# Display.net
KiCad netlist of a schematic drawn in Altium Designer
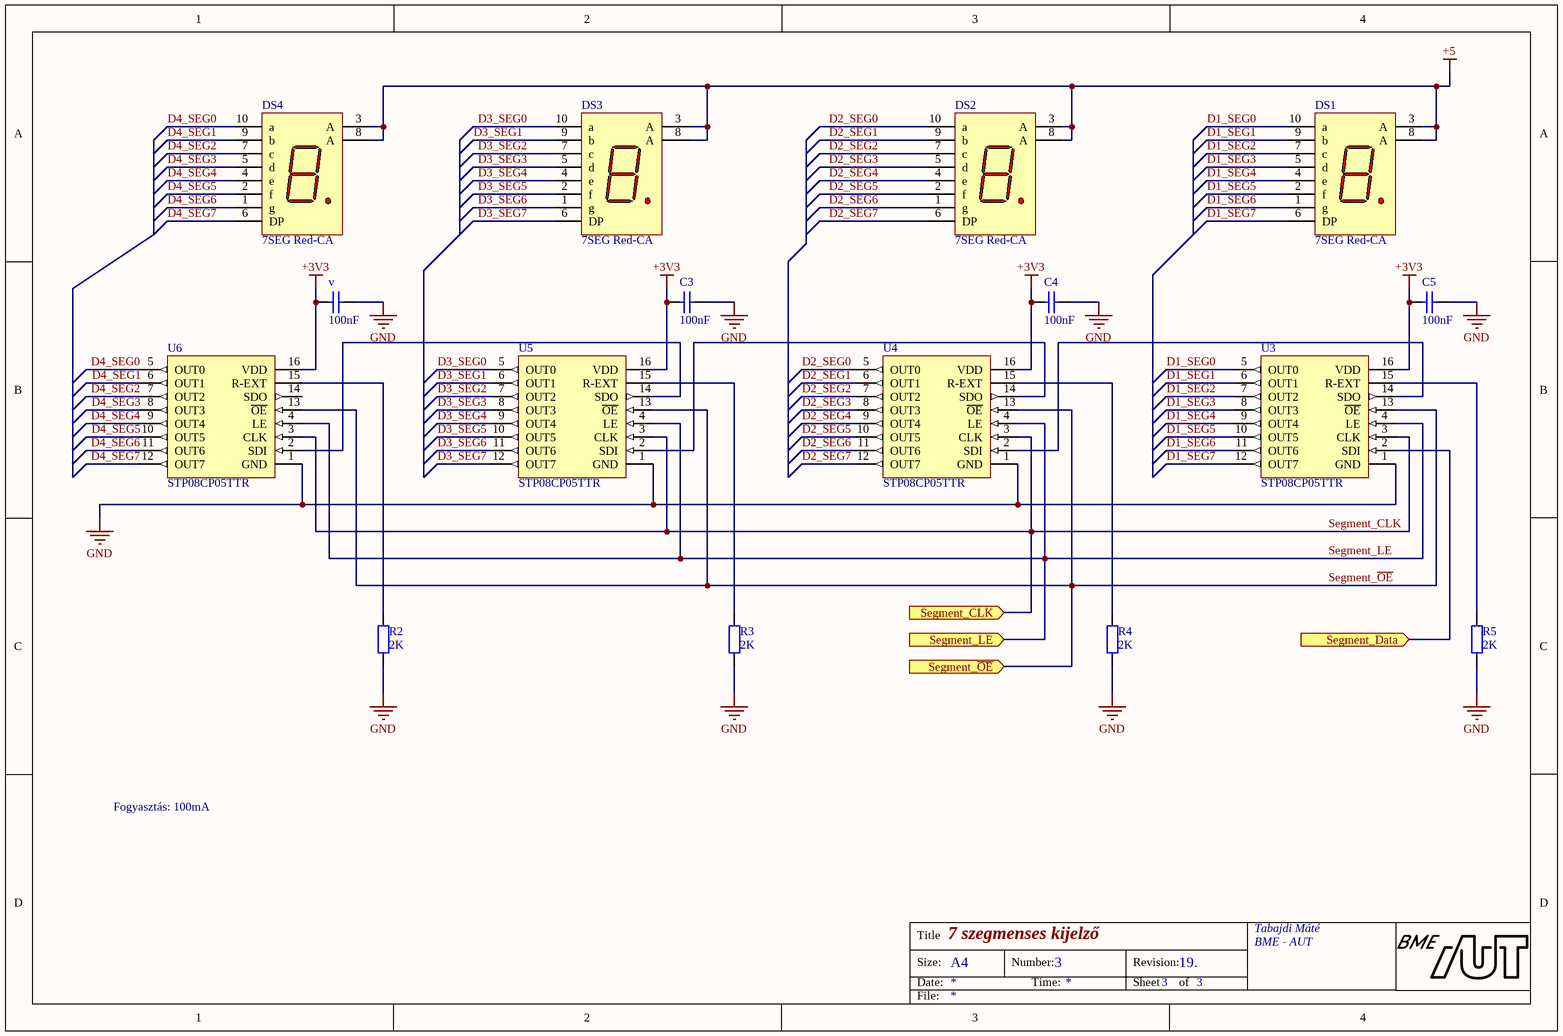
[diagram p0: Display.SchDoc]

(export (version "E")
  (design (tool "Eeschema 10.0.6"))
  (components
    (comp (ref "C3")
      (value "100nF")
      (footprint "FP_0805_CAP_085")
      (description "Capacitor")
      (fields (field (name "TOLERANCE") "10%") (field (name "VOLTAGE") "50V"))
      (libsource (lib "hallglib") (part "CAP"))
    )
    (comp (ref "C4")
      (value "100nF")
      (footprint "FP_0805_CAP_085")
      (description "Capacitor")
      (fields (field (name "TOLERANCE") "10%") (field (name "VOLTAGE") "50V"))
      (libsource (lib "hallglib") (part "CAP"))
    )
    (comp (ref "C5")
      (value "100nF")
      (footprint "FP_0805_CAP_085")
      (description "Capacitor")
      (fields (field (name "TOLERANCE") "10%") (field (name "VOLTAGE") "50V"))
      (libsource (lib "hallglib") (part "CAP"))
    )
    (comp (ref "DS1")
      (value "7SEG Red-CA")
      (footprint "FP_7SEG")
      (description "7-Segment Display: CA, RH DP")
      (fields (field (name "PUBLISHER") "Altium Limited"))
      (libsource (lib "hallglib") (part "7SEG Red-CA"))
    )
    (comp (ref "DS2")
      (value "7SEG Red-CA")
      (footprint "FP_7SEG")
      (description "7-Segment Display: CA, RH DP")
      (fields (field (name "PUBLISHER") "Altium Limited"))
      (libsource (lib "hallglib") (part "7SEG Red-CA"))
    )
    (comp (ref "DS3")
      (value "7SEG Red-CA")
      (footprint "FP_7SEG")
      (description "7-Segment Display: CA, RH DP")
      (fields (field (name "PUBLISHER") "Altium Limited"))
      (libsource (lib "hallglib") (part "7SEG Red-CA"))
    )
    (comp (ref "DS4")
      (value "7SEG Red-CA")
      (footprint "FP_7SEG")
      (description "7-Segment Display: CA, RH DP")
      (fields (field (name "PUBLISHER") "Altium Limited"))
      (libsource (lib "hallglib") (part "7SEG Red-CA"))
    )
    (comp (ref "R2")
      (value "2K")
      (footprint "FP_0805_RES")
      (description "Resistor")
      (fields (field (name "TOLERANCE") "5%") (field (name "POWER") "0.125W"))
      (libsource (lib "hallglib") (part "RES"))
    )
    (comp (ref "R3")
      (value "2K")
      (footprint "FP_0805_RES")
      (description "Resistor")
      (fields (field (name "TOLERANCE") "5%") (field (name "POWER") "0.125W"))
      (libsource (lib "hallglib") (part "RES"))
    )
    (comp (ref "R4")
      (value "2K")
      (footprint "FP_0805_RES")
      (description "Resistor")
      (fields (field (name "TOLERANCE") "5%") (field (name "POWER") "0.125W"))
      (libsource (lib "hallglib") (part "RES"))
    )
    (comp (ref "R5")
      (value "2K")
      (footprint "FP_0805_RES")
      (description "Resistor")
      (fields (field (name "TOLERANCE") "5%") (field (name "POWER") "0.125W"))
      (libsource (lib "hallglib") (part "RES"))
    )
    (comp (ref "U3")
      (value "STP08CP05TTR")
      (footprint "TSOP65P640X120-16M")
      (description "Low voltage, low current power 8-bit shift register")
      (libsource (lib "hallglib") (part "STP08CP05TTR"))
    )
    (comp (ref "U4")
      (value "STP08CP05TTR")
      (footprint "TSOP65P640X120-16M")
      (description "Low voltage, low current power 8-bit shift register")
      (libsource (lib "hallglib") (part "STP08CP05TTR"))
    )
    (comp (ref "U5")
      (value "STP08CP05TTR")
      (footprint "TSOP65P640X120-16M")
      (description "Low voltage, low current power 8-bit shift register")
      (libsource (lib "hallglib") (part "STP08CP05TTR"))
    )
    (comp (ref "U6")
      (value "STP08CP05TTR")
      (footprint "TSOP65P640X120-16M")
      (description "Low voltage, low current power 8-bit shift register")
      (libsource (lib "hallglib") (part "STP08CP05TTR"))
    )
    (comp (ref "v")
      (value "100nF")
      (footprint "FP_0805_CAP_085")
      (description "Capacitor")
      (fields (field (name "TOLERANCE") "10%") (field (name "VOLTAGE") "50V"))
      (libsource (lib "hallglib") (part "CAP"))
    )
  )
  (nets
    (net (code "1") (name "+3V3") (class "Default")
      (node (ref "C3") (pin "2") (pinfunction "2_2") (pintype "passive"))
      (node (ref "C4") (pin "2") (pinfunction "2_2") (pintype "passive"))
      (node (ref "C5") (pin "2") (pinfunction "2_2") (pintype "passive"))
      (node (ref "U3") (pin "16") (pinfunction "VDD_16") (pintype "power_in"))
      (node (ref "U4") (pin "16") (pinfunction "VDD_16") (pintype "power_in"))
      (node (ref "U5") (pin "16") (pinfunction "VDD_16") (pintype "power_in"))
      (node (ref "U6") (pin "16") (pinfunction "VDD_16") (pintype "power_in"))
      (node (ref "v") (pin "2") (pinfunction "2_2") (pintype "passive"))
    )
    (net (code "2") (name "+5") (class "Default")
      (node (ref "DS1") (pin "3") (pinfunction "A_3") (pintype "passive"))
      (node (ref "DS1") (pin "8") (pinfunction "A_8") (pintype "passive"))
      (node (ref "DS2") (pin "3") (pinfunction "A_3") (pintype "passive"))
      (node (ref "DS2") (pin "8") (pinfunction "A_8") (pintype "passive"))
      (node (ref "DS3") (pin "3") (pinfunction "A_3") (pintype "passive"))
      (node (ref "DS3") (pin "8") (pinfunction "A_8") (pintype "passive"))
      (node (ref "DS4") (pin "3") (pinfunction "A_3") (pintype "passive"))
      (node (ref "DS4") (pin "8") (pinfunction "A_8") (pintype "passive"))
    )
    (net (code "3") (name "/D1_SEG0") (class "Default")
      (node (ref "DS1") (pin "10") (pinfunction "a_10") (pintype "passive"))
      (node (ref "U3") (pin "5") (pinfunction "OUT0_5") (pintype "output"))
    )
    (net (code "4") (name "/D1_SEG1") (class "Default")
      (node (ref "DS1") (pin "9") (pinfunction "b_9") (pintype "passive"))
      (node (ref "U3") (pin "6") (pinfunction "OUT1_6") (pintype "output"))
    )
    (net (code "5") (name "/D1_SEG2") (class "Default")
      (node (ref "DS1") (pin "7") (pinfunction "c_7") (pintype "passive"))
      (node (ref "U3") (pin "7") (pinfunction "OUT2_7") (pintype "output"))
    )
    (net (code "6") (name "/D1_SEG3") (class "Default")
      (node (ref "DS1") (pin "5") (pinfunction "d_5") (pintype "passive"))
      (node (ref "U3") (pin "8") (pinfunction "OUT3_8") (pintype "output"))
    )
    (net (code "7") (name "/D1_SEG4") (class "Default")
      (node (ref "DS1") (pin "4") (pinfunction "e_4") (pintype "passive"))
      (node (ref "U3") (pin "9") (pinfunction "OUT4_9") (pintype "output"))
    )
    (net (code "8") (name "/D1_SEG5") (class "Default")
      (node (ref "DS1") (pin "2") (pinfunction "f_2") (pintype "passive"))
      (node (ref "U3") (pin "10") (pinfunction "OUT5_10") (pintype "output"))
    )
    (net (code "9") (name "/D1_SEG6") (class "Default")
      (node (ref "DS1") (pin "1") (pinfunction "g_1") (pintype "passive"))
      (node (ref "U3") (pin "11") (pinfunction "OUT6_11") (pintype "output"))
    )
    (net (code "10") (name "/D1_SEG7") (class "Default")
      (node (ref "DS1") (pin "6") (pinfunction "DP_6") (pintype "passive"))
      (node (ref "U3") (pin "12") (pinfunction "OUT7_12") (pintype "output"))
    )
    (net (code "11") (name "/D2_SEG0") (class "Default")
      (node (ref "DS2") (pin "10") (pinfunction "a_10") (pintype "passive"))
      (node (ref "U4") (pin "5") (pinfunction "OUT0_5") (pintype "output"))
    )
    (net (code "12") (name "/D2_SEG1") (class "Default")
      (node (ref "DS2") (pin "9") (pinfunction "b_9") (pintype "passive"))
      (node (ref "U4") (pin "6") (pinfunction "OUT1_6") (pintype "output"))
    )
    (net (code "13") (name "/D2_SEG2") (class "Default")
      (node (ref "DS2") (pin "7") (pinfunction "c_7") (pintype "passive"))
      (node (ref "U4") (pin "7") (pinfunction "OUT2_7") (pintype "output"))
    )
    (net (code "14") (name "/D2_SEG3") (class "Default")
      (node (ref "DS2") (pin "5") (pinfunction "d_5") (pintype "passive"))
      (node (ref "U4") (pin "8") (pinfunction "OUT3_8") (pintype "output"))
    )
    (net (code "15") (name "/D2_SEG4") (class "Default")
      (node (ref "DS2") (pin "4") (pinfunction "e_4") (pintype "passive"))
      (node (ref "U4") (pin "9") (pinfunction "OUT4_9") (pintype "output"))
    )
    (net (code "16") (name "/D2_SEG5") (class "Default")
      (node (ref "DS2") (pin "2") (pinfunction "f_2") (pintype "passive"))
      (node (ref "U4") (pin "10") (pinfunction "OUT5_10") (pintype "output"))
    )
    (net (code "17") (name "/D2_SEG6") (class "Default")
      (node (ref "DS2") (pin "1") (pinfunction "g_1") (pintype "passive"))
      (node (ref "U4") (pin "11") (pinfunction "OUT6_11") (pintype "output"))
    )
    (net (code "18") (name "/D2_SEG7") (class "Default")
      (node (ref "DS2") (pin "6") (pinfunction "DP_6") (pintype "passive"))
      (node (ref "U4") (pin "12") (pinfunction "OUT7_12") (pintype "output"))
    )
    (net (code "19") (name "/D3_SEG0") (class "Default")
      (node (ref "DS3") (pin "10") (pinfunction "a_10") (pintype "passive"))
      (node (ref "U5") (pin "5") (pinfunction "OUT0_5") (pintype "output"))
    )
    (net (code "20") (name "/D3_SEG1") (class "Default")
      (node (ref "DS3") (pin "9") (pinfunction "b_9") (pintype "passive"))
      (node (ref "U5") (pin "6") (pinfunction "OUT1_6") (pintype "output"))
    )
    (net (code "21") (name "/D3_SEG2") (class "Default")
      (node (ref "DS3") (pin "7") (pinfunction "c_7") (pintype "passive"))
      (node (ref "U5") (pin "7") (pinfunction "OUT2_7") (pintype "output"))
    )
    (net (code "22") (name "/D3_SEG3") (class "Default")
      (node (ref "DS3") (pin "5") (pinfunction "d_5") (pintype "passive"))
      (node (ref "U5") (pin "8") (pinfunction "OUT3_8") (pintype "output"))
    )
    (net (code "23") (name "/D3_SEG4") (class "Default")
      (node (ref "DS3") (pin "4") (pinfunction "e_4") (pintype "passive"))
      (node (ref "U5") (pin "9") (pinfunction "OUT4_9") (pintype "output"))
    )
    (net (code "24") (name "/D3_SEG5") (class "Default")
      (node (ref "DS3") (pin "2") (pinfunction "f_2") (pintype "passive"))
      (node (ref "U5") (pin "10") (pinfunction "OUT5_10") (pintype "output"))
    )
    (net (code "25") (name "/D3_SEG6") (class "Default")
      (node (ref "DS3") (pin "1") (pinfunction "g_1") (pintype "passive"))
      (node (ref "U5") (pin "11") (pinfunction "OUT6_11") (pintype "output"))
    )
    (net (code "26") (name "/D3_SEG7") (class "Default")
      (node (ref "DS3") (pin "6") (pinfunction "DP_6") (pintype "passive"))
      (node (ref "U5") (pin "12") (pinfunction "OUT7_12") (pintype "output"))
    )
    (net (code "27") (name "/D4_SEG0") (class "Default")
      (node (ref "DS4") (pin "10") (pinfunction "a_10") (pintype "passive"))
      (node (ref "U6") (pin "5") (pinfunction "OUT0_5") (pintype "output"))
    )
    (net (code "28") (name "/D4_SEG1") (class "Default")
      (node (ref "DS4") (pin "9") (pinfunction "b_9") (pintype "passive"))
      (node (ref "U6") (pin "6") (pinfunction "OUT1_6") (pintype "output"))
    )
    (net (code "29") (name "/D4_SEG2") (class "Default")
      (node (ref "DS4") (pin "7") (pinfunction "c_7") (pintype "passive"))
      (node (ref "U6") (pin "7") (pinfunction "OUT2_7") (pintype "output"))
    )
    (net (code "30") (name "/D4_SEG3") (class "Default")
      (node (ref "DS4") (pin "5") (pinfunction "d_5") (pintype "passive"))
      (node (ref "U6") (pin "8") (pinfunction "OUT3_8") (pintype "output"))
    )
    (net (code "31") (name "/D4_SEG4") (class "Default")
      (node (ref "DS4") (pin "4") (pinfunction "e_4") (pintype "passive"))
      (node (ref "U6") (pin "9") (pinfunction "OUT4_9") (pintype "output"))
    )
    (net (code "32") (name "/D4_SEG5") (class "Default")
      (node (ref "DS4") (pin "2") (pinfunction "f_2") (pintype "passive"))
      (node (ref "U6") (pin "10") (pinfunction "OUT5_10") (pintype "output"))
    )
    (net (code "33") (name "/D4_SEG6") (class "Default")
      (node (ref "DS4") (pin "1") (pinfunction "g_1") (pintype "passive"))
      (node (ref "U6") (pin "11") (pinfunction "OUT6_11") (pintype "output"))
    )
    (net (code "34") (name "/D4_SEG7") (class "Default")
      (node (ref "DS4") (pin "6") (pinfunction "DP_6") (pintype "passive"))
      (node (ref "U6") (pin "12") (pinfunction "OUT7_12") (pintype "output"))
    )
    (net (code "35") (name "/Segment_CLK") (class "Default")
      (node (ref "U3") (pin "3") (pinfunction "CLK_3") (pintype "input"))
      (node (ref "U4") (pin "3") (pinfunction "CLK_3") (pintype "input"))
      (node (ref "U5") (pin "3") (pinfunction "CLK_3") (pintype "input"))
      (node (ref "U6") (pin "3") (pinfunction "CLK_3") (pintype "input"))
    )
    (net (code "36") (name "/Segment_Data") (class "Default")
      (node (ref "U3") (pin "2") (pinfunction "SDI_2") (pintype "input"))
    )
    (net (code "37") (name "/Segment_LE") (class "Default")
      (node (ref "U3") (pin "4") (pinfunction "LE_4") (pintype "input"))
      (node (ref "U4") (pin "4") (pinfunction "LE_4") (pintype "input"))
      (node (ref "U5") (pin "4") (pinfunction "LE_4") (pintype "input"))
      (node (ref "U6") (pin "4") (pinfunction "LE_4") (pintype "input"))
    )
    (net (code "38") (name "/Segment_~{OE}") (class "Default")
      (node (ref "U3") (pin "13") (pinfunction "~{OE}_13") (pintype "input"))
      (node (ref "U4") (pin "13") (pinfunction "~{OE}_13") (pintype "input"))
      (node (ref "U5") (pin "13") (pinfunction "~{OE}_13") (pintype "input"))
      (node (ref "U6") (pin "13") (pinfunction "~{OE}_13") (pintype "input"))
    )
    (net (code "39") (name "GND") (class "Default")
      (node (ref "C3") (pin "1") (pinfunction "1_1") (pintype "passive"))
      (node (ref "C4") (pin "1") (pinfunction "1_1") (pintype "passive"))
      (node (ref "C5") (pin "1") (pinfunction "1_1") (pintype "passive"))
      (node (ref "R2") (pin "1") (pinfunction "1_1") (pintype "passive"))
      (node (ref "R3") (pin "1") (pinfunction "1_1") (pintype "passive"))
      (node (ref "R4") (pin "1") (pinfunction "1_1") (pintype "passive"))
      (node (ref "R5") (pin "1") (pinfunction "1_1") (pintype "passive"))
      (node (ref "U3") (pin "1") (pinfunction "GND_1") (pintype "passive"))
      (node (ref "U4") (pin "1") (pinfunction "GND_1") (pintype "passive"))
      (node (ref "U5") (pin "1") (pinfunction "GND_1") (pintype "passive"))
      (node (ref "U6") (pin "1") (pinfunction "GND_1") (pintype "passive"))
      (node (ref "v") (pin "1") (pinfunction "1_1") (pintype "passive"))
    )
    (net (code "40") (name "Net-(U3-R-EXT)") (class "Default")
      (node (ref "R5") (pin "2") (pinfunction "2_2") (pintype "passive"))
      (node (ref "U3") (pin "15") (pinfunction "R-EXT_15") (pintype "passive"))
    )
    (net (code "41") (name "Net-(U3-SDO)") (class "Default")
      (node (ref "U3") (pin "14") (pinfunction "SDO_14") (pintype "output"))
      (node (ref "U4") (pin "2") (pinfunction "SDI_2") (pintype "input"))
    )
    (net (code "42") (name "Net-(U4-R-EXT)") (class "Default")
      (node (ref "R4") (pin "2") (pinfunction "2_2") (pintype "passive"))
      (node (ref "U4") (pin "15") (pinfunction "R-EXT_15") (pintype "passive"))
    )
    (net (code "43") (name "Net-(U4-SDO)") (class "Default")
      (node (ref "U4") (pin "14") (pinfunction "SDO_14") (pintype "output"))
      (node (ref "U5") (pin "2") (pinfunction "SDI_2") (pintype "input"))
    )
    (net (code "44") (name "Net-(U5-R-EXT)") (class "Default")
      (node (ref "R3") (pin "2") (pinfunction "2_2") (pintype "passive"))
      (node (ref "U5") (pin "15") (pinfunction "R-EXT_15") (pintype "passive"))
    )
    (net (code "45") (name "Net-(U5-SDO)") (class "Default")
      (node (ref "U5") (pin "14") (pinfunction "SDO_14") (pintype "output"))
      (node (ref "U6") (pin "2") (pinfunction "SDI_2") (pintype "input"))
    )
    (net (code "46") (name "Net-(U6-R-EXT)") (class "Default")
      (node (ref "R2") (pin "2") (pinfunction "2_2") (pintype "passive"))
      (node (ref "U6") (pin "15") (pinfunction "R-EXT_15") (pintype "passive"))
    )
    (net (code "47") (name "unconnected-(U6-SDO-Pad14)") (class "Default")
      (node (ref "U6") (pin "14") (pinfunction "SDO_14") (pintype "output"))
    )
  )
)
